# UART.net
KiCad netlist of a schematic drawn in Altium Designer
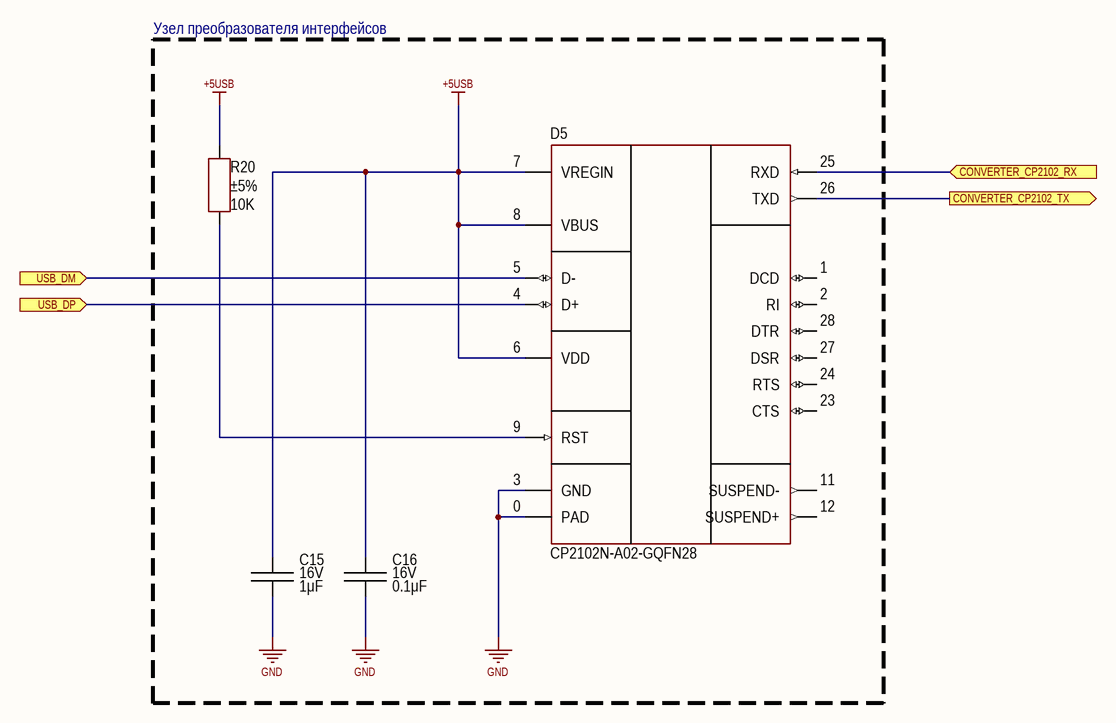
[diagram p0: Узел UART преобразователя.SchDoc]

(export (version "E")
  (design (tool "Eeschema 10.0.6"))
  (components
    (comp (ref "C15")
      (value "1μF")
      (footprint "CAP: 0603")
      (fields
        (field (name "MANUFACTURER") "Yageo")
        (field (name "PARTNUMBER") "CC0603KRX7R7BB104")
        (field (name "VALUEMANUFACTURERPARTNUMBER") "Ceramic capacitor, 1μF, X7R, ±10%, 16V, 0603, -55...+125°C")
        (field (name "VOLTAGE") "16V")
      )
      (libsource (lib "capacitor") (part "Ceramic_0603"))
    )
    (comp (ref "C16")
      (value "0.1μF")
      (footprint "CAP: 0603")
      (fields
        (field (name "MANUFACTURER") "Yageo")
        (field (name "PARTNUMBER") "CC0603KRX7R7BB104")
        (field (name "VALUEMANUFACTURERPARTNUMBER") "Ceramic capacitor, 0.1μF, X7R, ±10%, 16V, 0603, -55...+125°C")
        (field (name "VOLTAGE") "16V")
      )
      (libsource (lib "capacitor") (part "Ceramic_0603"))
    )
    (comp (ref "D5")
      (value "~")
      (footprint "28-QFN (5x5)")
      (description "USB-to-UART")
      (fields
        (field (name "MANUFACTURER") "Silicon Labs")
        (field (name "VALUEMANUFACTURERPARTNUMBER") "IC usb-to-uart bridge, USB2.0, 3...3.6V, -40...+85°C, 28-VFQFN")
        (field (name "PARTNUMBER") "CP2102N-A02-GQFN28")
      )
      (libsource (lib "ic-interface") (part "CP2102N"))
    )
    (comp (ref "R20")
      (value "10K")
      (footprint "RES: 0603")
      (fields
        (field (name "MANUFACTURER") "Yageo")
        (field (name "PARTNUMBER") "RC0603JR-07100RL")
        (field (name "VALUEMANUFACTURERPARTNUMBER") "Resistor film, 10K, ±5%, 0603, 0.1W, -55...+125°C")
        (field (name "TOLERANCE") "±5%")
      )
      (libsource (lib "resistor") (part "Resistor_0603"))
    )
  )
  (nets
    (net (code "1") (name "+5USB") (class "Default")
      (node (ref "C15") (pin "2") (pinfunction "2_2") (pintype "passive"))
      (node (ref "C16") (pin "2") (pinfunction "2_2") (pintype "passive"))
      (node (ref "D5") (pin "6") (pinfunction "VDD_6") (pintype "passive"))
      (node (ref "D5") (pin "7") (pinfunction "VREGIN_7") (pintype "passive"))
      (node (ref "D5") (pin "8") (pinfunction "VBUS_8") (pintype "passive"))
      (node (ref "R20") (pin "2") (pinfunction "2_2") (pintype "passive"))
    )
    (net (code "2") (name "/CONVERTER_CP2102_RX") (class "Default")
      (node (ref "D5") (pin "25") (pinfunction "RXD_25") (pintype "input"))
    )
    (net (code "3") (name "/CONVERTER_CP2102_TX") (class "Default")
      (node (ref "D5") (pin "26") (pinfunction "TXD_26") (pintype "output"))
    )
    (net (code "4") (name "/USB_DM") (class "Default")
      (node (ref "D5") (pin "5") (pinfunction "D-_5") (pintype "bidirectional"))
    )
    (net (code "5") (name "/USB_DP") (class "Default")
      (node (ref "D5") (pin "4") (pinfunction "D+_4") (pintype "bidirectional"))
    )
    (net (code "6") (name "GND") (class "Default")
      (node (ref "C15") (pin "1") (pinfunction "1_1") (pintype "passive"))
      (node (ref "C16") (pin "1") (pinfunction "1_1") (pintype "passive"))
      (node (ref "D5") (pin "0") (pinfunction "PAD_0") (pintype "passive"))
      (node (ref "D5") (pin "3") (pinfunction "GND_3") (pintype "passive"))
    )
    (net (code "7") (name "Net-(D5-RST)") (class "Default")
      (node (ref "D5") (pin "9") (pinfunction "RST_9") (pintype "input"))
      (node (ref "R20") (pin "1") (pinfunction "1_1") (pintype "passive"))
    )
    (net (code "8") (name "unconnected-(D5-CTS-Pad23)") (class "Default")
      (node (ref "D5") (pin "23") (pinfunction "CTS_23") (pintype "bidirectional"))
    )
    (net (code "9") (name "unconnected-(D5-DCD-Pad1)") (class "Default")
      (node (ref "D5") (pin "1") (pinfunction "DCD_1") (pintype "bidirectional"))
    )
    (net (code "10") (name "unconnected-(D5-DSR-Pad27)") (class "Default")
      (node (ref "D5") (pin "27") (pinfunction "DSR_27") (pintype "bidirectional"))
    )
    (net (code "11") (name "unconnected-(D5-DTR-Pad28)") (class "Default")
      (node (ref "D5") (pin "28") (pinfunction "DTR_28") (pintype "bidirectional"))
    )
    (net (code "12") (name "unconnected-(D5-RI-Pad2)") (class "Default")
      (node (ref "D5") (pin "2") (pinfunction "RI_2") (pintype "bidirectional"))
    )
    (net (code "13") (name "unconnected-(D5-RTS-Pad24)") (class "Default")
      (node (ref "D5") (pin "24") (pinfunction "RTS_24") (pintype "bidirectional"))
    )
    (net (code "14") (name "unconnected-(D5-SUSPEND+-Pad12)") (class "Default")
      (node (ref "D5") (pin "12") (pinfunction "SUSPEND+_12") (pintype "output"))
    )
    (net (code "15") (name "unconnected-(D5-SUSPEND--Pad11)") (class "Default")
      (node (ref "D5") (pin "11") (pinfunction "SUSPEND-_11") (pintype "output"))
    )
  )
)
